# Piezo_signal_amp_filter_v0_1.net
KiCad netlist of a schematic drawn in EAGLE
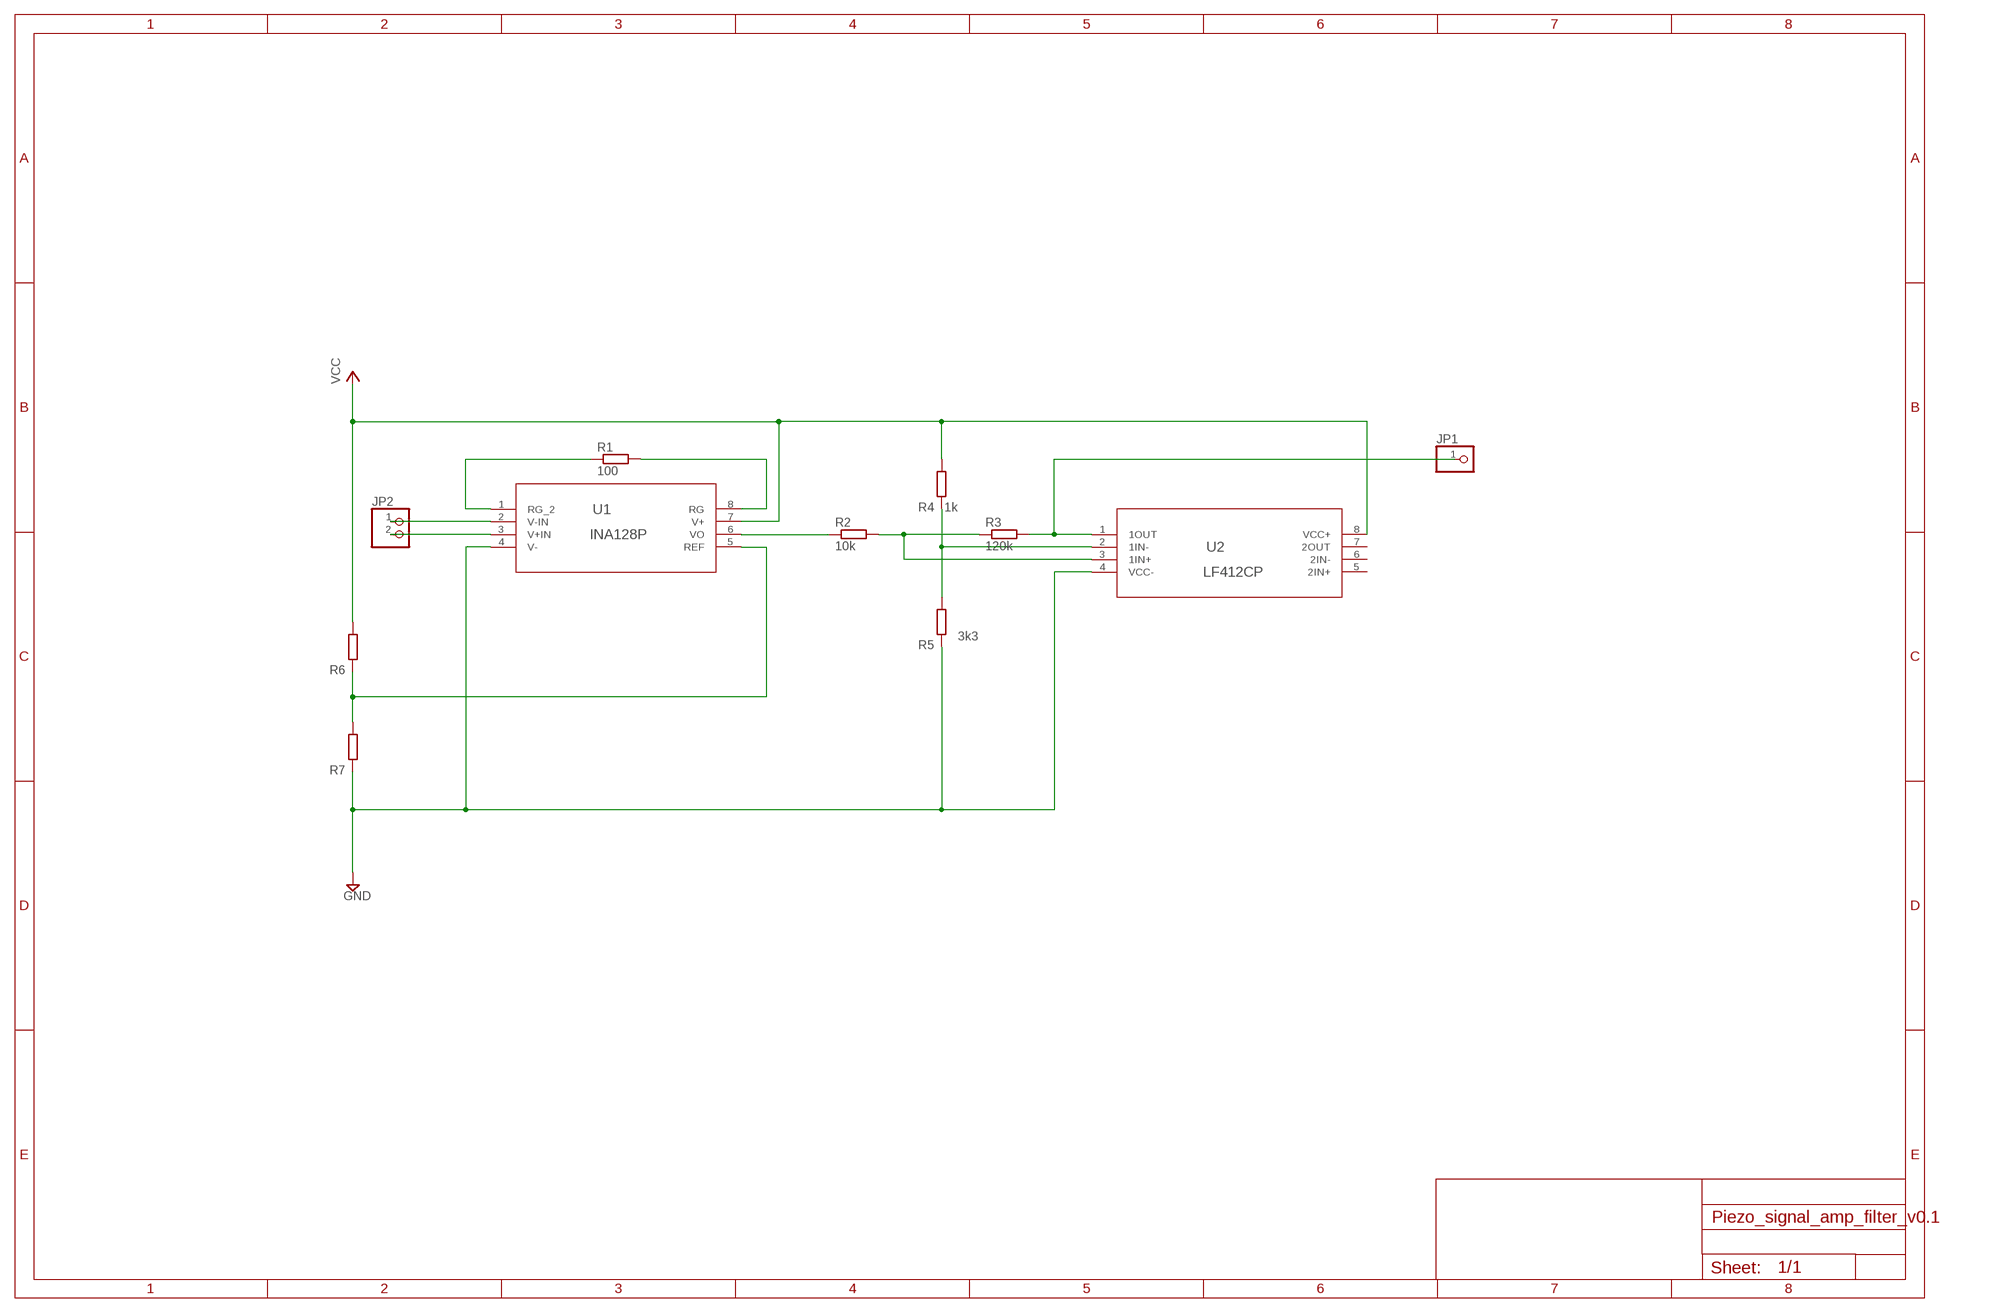
[diagram p0: schematic, sheet 1]

(export (version "E")
  (design (tool "Eeschema 10.0.6"))
  (components
    (comp (ref "JP1")
      (value "PINHD-1X1")
      (footprint "eagle-import:1X01")
      (libsource (lib "eagle-import") (part "PINHD-1X1"))
    )
    (comp (ref "JP2")
      (value "PINHD-1X2")
      (footprint "eagle-import:1X02")
      (libsource (lib "eagle-import") (part "PINHD-1X2"))
    )
    (comp (ref "R1")
      (value "100")
      (footprint "eagle-import:0207_10")
      (libsource (lib "eagle-import") (part "R-EU_0207/10"))
    )
    (comp (ref "R2")
      (value "10k")
      (footprint "eagle-import:0207_10")
      (libsource (lib "eagle-import") (part "R-EU_0207/10"))
    )
    (comp (ref "R3")
      (value "120k")
      (footprint "eagle-import:0207_10")
      (libsource (lib "eagle-import") (part "R-EU_0207/10"))
    )
    (comp (ref "R4")
      (value "1k")
      (footprint "eagle-import:0207_10")
      (libsource (lib "eagle-import") (part "R-EU_0207/10"))
    )
    (comp (ref "R5")
      (value "3k3")
      (footprint "eagle-import:0207_10")
      (libsource (lib "eagle-import") (part "R-EU_0207/10"))
    )
    (comp (ref "R6")
      (value "R-EU_0207/10")
      (footprint "eagle-import:0207_10")
      (libsource (lib "eagle-import") (part "R-EU_0207/10"))
    )
    (comp (ref "R7")
      (value "R-EU_0207/10")
      (footprint "eagle-import:0207_10")
      (libsource (lib "eagle-import") (part "R-EU_0207/10"))
    )
    (comp (ref "U1")
      (value "INA128P")
      (footprint "eagle-import:P8")
      (fields (field (name "GENERIC_PART_NUMBER") "INA128") (field (name "MANUFACTURER") "Texas Instruments"))
      (libsource (lib "eagle-import") (part "INA128P"))
    )
    (comp (ref "U2")
      (value "LF412CP")
      (footprint "eagle-import:P8")
      (fields (field (name "GENERIC_PART_NUMBER") "LF412") (field (name "MANUFACTURER") "Texas Instruments"))
      (libsource (lib "eagle-import") (part "LF412CP"))
    )
  )
  (nets
    (net (code "1") (name "GND") (class "Default")
      (node (ref "R5") (pin "1") (pinfunction "1_1") (pintype "passive"))
      (node (ref "R7") (pin "1") (pinfunction "1_1") (pintype "passive"))
      (node (ref "U1") (pin "4") (pinfunction "V-_4") (pintype "power_in"))
      (node (ref "U2") (pin "4") (pinfunction "VCC-_4") (pintype "passive"))
    )
    (net (code "2") (name "Net-(U1-REF)") (class "Default")
      (node (ref "R6") (pin "1") (pinfunction "1_1") (pintype "passive"))
      (node (ref "R7") (pin "2") (pinfunction "2_2") (pintype "passive"))
      (node (ref "U1") (pin "5") (pinfunction "REF_5") (pintype "passive"))
    )
    (net (code "3") (name "Net-(U1-RG)") (class "Default")
      (node (ref "R1") (pin "2") (pinfunction "2_2") (pintype "passive"))
      (node (ref "U1") (pin "8") (pinfunction "RG_8") (pintype "passive"))
    )
    (net (code "4") (name "Net-(U1-RG_2)") (class "Default")
      (node (ref "R1") (pin "1") (pinfunction "1_1") (pintype "passive"))
      (node (ref "U1") (pin "1") (pinfunction "RG_2_1") (pintype "passive"))
    )
    (net (code "5") (name "Net-(U1-V+IN)") (class "Default")
      (node (ref "JP2") (pin "2") (pinfunction "2_2") (pintype "passive"))
      (node (ref "U1") (pin "3") (pinfunction "V+IN_3") (pintype "input"))
    )
    (net (code "6") (name "Net-(U1-V-IN)") (class "Default")
      (node (ref "JP2") (pin "1") (pinfunction "1_1") (pintype "passive"))
      (node (ref "U1") (pin "2") (pinfunction "V-IN_2") (pintype "input"))
    )
    (net (code "7") (name "Net-(U1-VO)") (class "Default")
      (node (ref "R2") (pin "1") (pinfunction "1_1") (pintype "passive"))
      (node (ref "U1") (pin "6") (pinfunction "VO_6") (pintype "output"))
    )
    (net (code "8") (name "Net-(U2-1IN+)") (class "Default")
      (node (ref "R2") (pin "2") (pinfunction "2_2") (pintype "passive"))
      (node (ref "R3") (pin "1") (pinfunction "1_1") (pintype "passive"))
      (node (ref "U2") (pin "3") (pinfunction "1IN+_3") (pintype "input"))
    )
    (net (code "9") (name "Net-(U2-1IN-)") (class "Default")
      (node (ref "R4") (pin "1") (pinfunction "1_1") (pintype "passive"))
      (node (ref "R5") (pin "2") (pinfunction "2_2") (pintype "passive"))
      (node (ref "U2") (pin "2") (pinfunction "1IN-_2") (pintype "input"))
    )
    (net (code "10") (name "Net-(U2-1OUT)") (class "Default")
      (node (ref "JP1") (pin "1") (pinfunction "1_1") (pintype "passive"))
      (node (ref "R3") (pin "2") (pinfunction "2_2") (pintype "passive"))
      (node (ref "U2") (pin "1") (pinfunction "1OUT_1") (pintype "output"))
    )
    (net (code "11") (name "VCC") (class "Default")
      (node (ref "R4") (pin "2") (pinfunction "2_2") (pintype "passive"))
      (node (ref "R6") (pin "2") (pinfunction "2_2") (pintype "passive"))
      (node (ref "U1") (pin "7") (pinfunction "V+_7") (pintype "power_in"))
      (node (ref "U2") (pin "8") (pinfunction "VCC+_8") (pintype "passive"))
    )
    (net (code "12") (name "unconnected-(U2-2IN+-Pad5)") (class "Default")
      (node (ref "U2") (pin "5") (pinfunction "2IN+_5") (pintype "input"))
    )
    (net (code "13") (name "unconnected-(U2-2IN--Pad6)") (class "Default")
      (node (ref "U2") (pin "6") (pinfunction "2IN-_6") (pintype "input"))
    )
    (net (code "14") (name "unconnected-(U2-2OUT-Pad7)") (class "Default")
      (node (ref "U2") (pin "7") (pinfunction "2OUT_7") (pintype "output"))
    )
  )
)
